# Power.net
KiCad netlist of a schematic drawn in Altium Designer
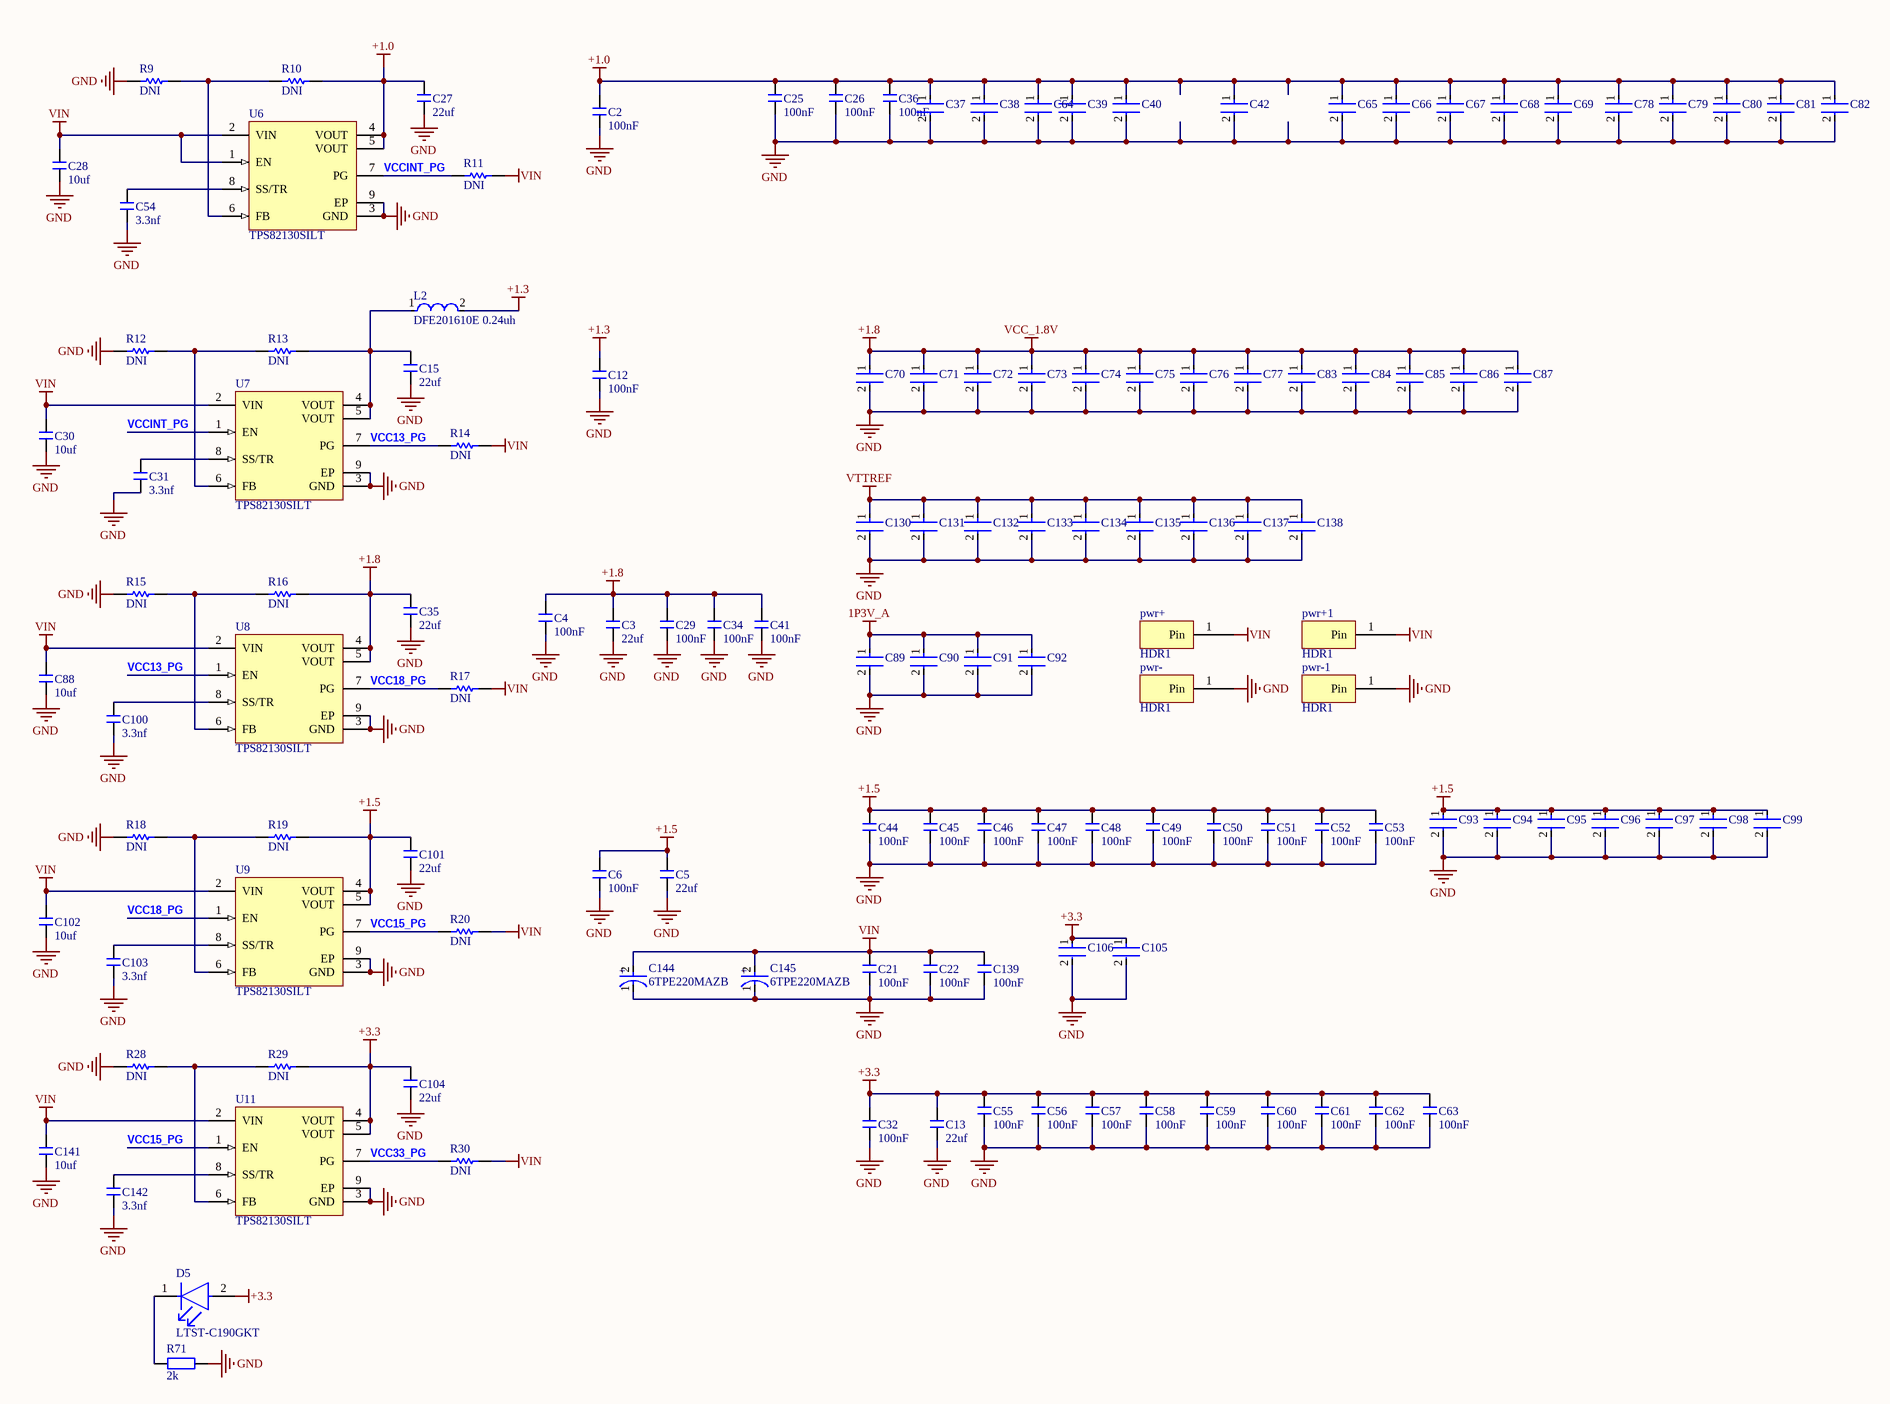
[diagram p0: Power.SchDoc]

(export (version "E")
  (design (tool "Eeschema 10.0.6"))
  (components
    (comp (ref "C2")
      (value "100nF")
      (footprint "SamacSys:CAP_0402")
      (description "无极性贴片电容")
      (libsource (lib "源创客") (part "C"))
    )
    (comp (ref "C3")
      (value "22uf")
      (footprint "SamacSys:CAP_0603")
      (description "无极性贴片电容")
      (libsource (lib "源创客") (part "C"))
    )
    (comp (ref "C4")
      (value "100nF")
      (footprint "SamacSys:CAP_0402")
      (description "无极性贴片电容")
      (libsource (lib "源创客") (part "C"))
    )
    (comp (ref "C5")
      (value "22uf")
      (footprint "SamacSys:CAP_0603")
      (description "无极性贴片电容")
      (libsource (lib "源创客") (part "C"))
    )
    (comp (ref "C6")
      (value "100nF")
      (footprint "SamacSys:CAP_0402")
      (description "无极性贴片电容")
      (libsource (lib "源创客") (part "C"))
    )
    (comp (ref "C12")
      (value "100nF")
      (footprint "SamacSys:CAP_0402")
      (description "无极性贴片电容")
      (libsource (lib "源创客") (part "C"))
    )
    (comp (ref "C13")
      (value "22uf")
      (footprint "SamacSys:CAP_0603")
      (description "无极性贴片电容")
      (libsource (lib "源创客") (part "C"))
    )
    (comp (ref "C15")
      (value "22uf")
      (footprint "SamacSys:CAP_0603")
      (description "无极性贴片电容")
      (libsource (lib "源创客") (part "C"))
    )
    (comp (ref "C21")
      (value "100nF")
      (footprint "SamacSys:CAP_0402")
      (description "无极性贴片电容")
      (libsource (lib "源创客") (part "C"))
    )
    (comp (ref "C22")
      (value "100nF")
      (footprint "SamacSys:CAP_0402")
      (description "无极性贴片电容")
      (libsource (lib "源创客") (part "C"))
    )
    (comp (ref "C25")
      (value "100nF")
      (footprint "SamacSys:CAP_0402")
      (description "无极性贴片电容")
      (libsource (lib "源创客") (part "C"))
    )
    (comp (ref "C26")
      (value "100nF")
      (footprint "SamacSys:CAP_0402")
      (description "无极性贴片电容")
      (libsource (lib "源创客") (part "C"))
    )
    (comp (ref "C27")
      (value "22uf")
      (footprint "SamacSys:CAP_0603")
      (description "无极性贴片电容")
      (libsource (lib "源创客") (part "C"))
    )
    (comp (ref "C28")
      (value "10uf")
      (footprint "SamacSys:CAP_0603")
      (description "无极性贴片电容")
      (libsource (lib "源创客") (part "C"))
    )
    (comp (ref "C29")
      (value "100nF")
      (footprint "SamacSys:CAP_0201")
      (description "无极性贴片电容")
      (libsource (lib "源创客") (part "C"))
    )
    (comp (ref "C30")
      (value "10uf")
      (footprint "SamacSys:CAP_0603")
      (description "无极性贴片电容")
      (libsource (lib "源创客") (part "C"))
    )
    (comp (ref "C31")
      (value "3.3nf")
      (footprint "SamacSys:CAP_0402")
      (description "无极性贴片电容")
      (libsource (lib "源创客") (part "C"))
    )
    (comp (ref "C32")
      (value "100nF")
      (footprint "SamacSys:CAP_0201")
      (description "无极性贴片电容")
      (libsource (lib "源创客") (part "C"))
    )
    (comp (ref "C34")
      (value "100nF")
      (footprint "SamacSys:CAP_0201")
      (description "无极性贴片电容")
      (libsource (lib "源创客") (part "C"))
    )
    (comp (ref "C35")
      (value "22uf")
      (footprint "SamacSys:CAP_0603")
      (description "无极性贴片电容")
      (libsource (lib "源创客") (part "C"))
    )
    (comp (ref "C36")
      (value "100nF")
      (footprint "SamacSys:CAP_0402")
      (description "无极性贴片电容")
      (libsource (lib "源创客") (part "C"))
    )
    (comp (ref "C37")
      (value "GRM033R61A104KE15D")
      (footprint "FP-GRM033-0_03-IPC_C")
      (description "Chip Multilayer Ceramic Capacitors for General Purpose, 0201, 0.10uF, X5R, 15%, 10%, 10V")
      (fields (field (name "TOLERANCE") "10%") (field (name "VOLTAGE") "10V"))
      (libsource (lib "Altium Content Vault") (part "b4654b650e69147ec39a6b967a45e02"))
    )
    (comp (ref "C38")
      (value "GRM033R61A104KE15D")
      (footprint "FP-GRM033-0_03-IPC_C")
      (description "Chip Multilayer Ceramic Capacitors for General Purpose, 0201, 0.10uF, X5R, 15%, 10%, 10V")
      (fields (field (name "TOLERANCE") "10%") (field (name "VOLTAGE") "10V"))
      (libsource (lib "Altium Content Vault") (part "b4654b650e69147ec39a6b967a45e02"))
    )
    (comp (ref "C39")
      (value "GRM033R61A104KE15D")
      (footprint "FP-GRM033-0_03-IPC_C")
      (description "Chip Multilayer Ceramic Capacitors for General Purpose, 0201, 0.10uF, X5R, 15%, 10%, 10V")
      (fields (field (name "TOLERANCE") "10%") (field (name "VOLTAGE") "10V"))
      (libsource (lib "Altium Content Vault") (part "b4654b650e69147ec39a6b967a45e02"))
    )
    (comp (ref "C40")
      (value "GRM033R61A104KE15D")
      (footprint "FP-GRM033-0_03-IPC_C")
      (description "Chip Multilayer Ceramic Capacitors for General Purpose, 0201, 0.10uF, X5R, 15%, 10%, 10V")
      (fields (field (name "TOLERANCE") "10%") (field (name "VOLTAGE") "10V"))
      (libsource (lib "Altium Content Vault") (part "b4654b650e69147ec39a6b967a45e02"))
    )
    (comp (ref "C41")
      (value "100nF")
      (footprint "SamacSys:CAP_0201")
      (description "无极性贴片电容")
      (libsource (lib "源创客") (part "C"))
    )
    (comp (ref "C42")
      (value "GRM033R61A104KE15D")
      (footprint "FP-GRM033-0_03-IPC_C")
      (description "Chip Multilayer Ceramic Capacitors for General Purpose, 0201, 0.10uF, X5R, 15%, 10%, 10V")
      (fields (field (name "TOLERANCE") "10%") (field (name "VOLTAGE") "10V"))
      (libsource (lib "Altium Content Vault") (part "b4654b650e69147ec39a6b967a45e02"))
    )
    (comp (ref "C44")
      (value "100nF")
      (footprint "SamacSys:CAP_0402")
      (description "无极性贴片电容")
      (libsource (lib "源创客") (part "C"))
    )
    (comp (ref "C45")
      (value "100nF")
      (footprint "SamacSys:CAP_0402")
      (description "无极性贴片电容")
      (libsource (lib "源创客") (part "C"))
    )
    (comp (ref "C46")
      (value "100nF")
      (footprint "SamacSys:CAP_0402")
      (description "无极性贴片电容")
      (libsource (lib "源创客") (part "C"))
    )
    (comp (ref "C47")
      (value "100nF")
      (footprint "SamacSys:CAP_0402")
      (description "无极性贴片电容")
      (libsource (lib "源创客") (part "C"))
    )
    (comp (ref "C48")
      (value "100nF")
      (footprint "SamacSys:CAP_0402")
      (description "无极性贴片电容")
      (libsource (lib "源创客") (part "C"))
    )
    (comp (ref "C49")
      (value "100nF")
      (footprint "SamacSys:CAP_0402")
      (description "无极性贴片电容")
      (libsource (lib "源创客") (part "C"))
    )
    (comp (ref "C50")
      (value "100nF")
      (footprint "SamacSys:CAP_0402")
      (description "无极性贴片电容")
      (libsource (lib "源创客") (part "C"))
    )
    (comp (ref "C51")
      (value "100nF")
      (footprint "SamacSys:CAP_0402")
      (description "无极性贴片电容")
      (libsource (lib "源创客") (part "C"))
    )
    (comp (ref "C52")
      (value "100nF")
      (footprint "SamacSys:CAP_0402")
      (description "无极性贴片电容")
      (libsource (lib "源创客") (part "C"))
    )
    (comp (ref "C53")
      (value "100nF")
      (footprint "SamacSys:CAP_0402")
      (description "无极性贴片电容")
      (libsource (lib "源创客") (part "C"))
    )
    (comp (ref "C54")
      (value "3.3nf")
      (footprint "SamacSys:CAP_0402")
      (description "无极性贴片电容")
      (libsource (lib "源创客") (part "C"))
    )
    (comp (ref "C55")
      (value "100nF")
      (footprint "SamacSys:CAP_0402")
      (description "无极性贴片电容")
      (libsource (lib "源创客") (part "C"))
    )
    (comp (ref "C56")
      (value "100nF")
      (footprint "SamacSys:CAP_0402")
      (description "无极性贴片电容")
      (libsource (lib "源创客") (part "C"))
    )
    (comp (ref "C57")
      (value "100nF")
      (footprint "SamacSys:CAP_0402")
      (description "无极性贴片电容")
      (libsource (lib "源创客") (part "C"))
    )
    (comp (ref "C58")
      (value "100nF")
      (footprint "SamacSys:CAP_0402")
      (description "无极性贴片电容")
      (libsource (lib "源创客") (part "C"))
    )
    (comp (ref "C59")
      (value "100nF")
      (footprint "SamacSys:CAP_0201")
      (description "无极性贴片电容")
      (libsource (lib "源创客") (part "C"))
    )
    (comp (ref "C60")
      (value "100nF")
      (footprint "SamacSys:CAP_0201")
      (description "无极性贴片电容")
      (libsource (lib "源创客") (part "C"))
    )
    (comp (ref "C61")
      (value "100nF")
      (footprint "SamacSys:CAP_0201")
      (description "无极性贴片电容")
      (libsource (lib "源创客") (part "C"))
    )
    (comp (ref "C62")
      (value "100nF")
      (footprint "SamacSys:CAP_0402")
      (description "无极性贴片电容")
      (libsource (lib "源创客") (part "C"))
    )
    (comp (ref "C63")
      (value "100nF")
      (footprint "SamacSys:CAP_0402")
      (description "无极性贴片电容")
      (libsource (lib "源创客") (part "C"))
    )
    (comp (ref "C64")
      (value "GRM033R61A104KE15D")
      (footprint "FP-GRM033-0_03-IPC_C")
      (description "Chip Multilayer Ceramic Capacitors for General Purpose, 0201, 0.10uF, X5R, 15%, 10%, 10V")
      (fields (field (name "TOLERANCE") "10%") (field (name "VOLTAGE") "10V"))
      (libsource (lib "Altium Content Vault") (part "b4654b650e69147ec39a6b967a45e02"))
    )
    (comp (ref "C65")
      (value "GRM033R61A104KE15D")
      (footprint "FP-GRM033-0_03-IPC_C")
      (description "Chip Multilayer Ceramic Capacitors for General Purpose, 0201, 0.10uF, X5R, 15%, 10%, 10V")
      (fields (field (name "TOLERANCE") "10%") (field (name "VOLTAGE") "10V"))
      (libsource (lib "Altium Content Vault") (part "b4654b650e69147ec39a6b967a45e02"))
    )
    (comp (ref "C66")
      (value "GRM033R61A104KE15D")
      (footprint "FP-GRM033-0_03-IPC_C")
      (description "Chip Multilayer Ceramic Capacitors for General Purpose, 0201, 0.10uF, X5R, 15%, 10%, 10V")
      (fields (field (name "TOLERANCE") "10%") (field (name "VOLTAGE") "10V"))
      (libsource (lib "Altium Content Vault") (part "b4654b650e69147ec39a6b967a45e02"))
    )
    (comp (ref "C67")
      (value "GRM033R61A104KE15D")
      (footprint "FP-GRM033-0_03-IPC_C")
      (description "Chip Multilayer Ceramic Capacitors for General Purpose, 0201, 0.10uF, X5R, 15%, 10%, 10V")
      (fields (field (name "TOLERANCE") "10%") (field (name "VOLTAGE") "10V"))
      (libsource (lib "Altium Content Vault") (part "b4654b650e69147ec39a6b967a45e02"))
    )
    (comp (ref "C68")
      (value "GRM033R61A104KE15D")
      (footprint "FP-GRM033-0_03-IPC_C")
      (description "Chip Multilayer Ceramic Capacitors for General Purpose, 0201, 0.10uF, X5R, 15%, 10%, 10V")
      (fields (field (name "TOLERANCE") "10%") (field (name "VOLTAGE") "10V"))
      (libsource (lib "Altium Content Vault") (part "b4654b650e69147ec39a6b967a45e02"))
    )
    (comp (ref "C69")
      (value "GRM033R61A104KE15D")
      (footprint "FP-GRM033-0_03-IPC_C")
      (description "Chip Multilayer Ceramic Capacitors for General Purpose, 0201, 0.10uF, X5R, 15%, 10%, 10V")
      (fields (field (name "TOLERANCE") "10%") (field (name "VOLTAGE") "10V"))
      (libsource (lib "Altium Content Vault") (part "b4654b650e69147ec39a6b967a45e02"))
    )
    (comp (ref "C70")
      (value "GRM033R61A104KE15D")
      (footprint "FP-GRM033-0_03-IPC_C")
      (description "Chip Multilayer Ceramic Capacitors for General Purpose, 0201, 0.10uF, X5R, 15%, 10%, 10V")
      (fields (field (name "TOLERANCE") "10%") (field (name "VOLTAGE") "10V"))
      (libsource (lib "Altium Content Vault") (part "b4654b650e69147ec39a6b967a45e02"))
    )
    (comp (ref "C71")
      (value "GRM033R61A104KE15D")
      (footprint "FP-GRM033-0_03-IPC_C")
      (description "Chip Multilayer Ceramic Capacitors for General Purpose, 0201, 0.10uF, X5R, 15%, 10%, 10V")
      (fields (field (name "TOLERANCE") "10%") (field (name "VOLTAGE") "10V"))
      (libsource (lib "Altium Content Vault") (part "b4654b650e69147ec39a6b967a45e02"))
    )
    (comp (ref "C72")
      (value "GRM033R61A104KE15D")
      (footprint "FP-GRM033-0_03-IPC_C")
      (description "Chip Multilayer Ceramic Capacitors for General Purpose, 0201, 0.10uF, X5R, 15%, 10%, 10V")
      (fields (field (name "TOLERANCE") "10%") (field (name "VOLTAGE") "10V"))
      (libsource (lib "Altium Content Vault") (part "b4654b650e69147ec39a6b967a45e02"))
    )
    (comp (ref "C73")
      (value "GRM033R61A104KE15D")
      (footprint "FP-GRM033-0_03-IPC_C")
      (description "Chip Multilayer Ceramic Capacitors for General Purpose, 0201, 0.10uF, X5R, 15%, 10%, 10V")
      (fields (field (name "TOLERANCE") "10%") (field (name "VOLTAGE") "10V"))
      (libsource (lib "Altium Content Vault") (part "b4654b650e69147ec39a6b967a45e02"))
    )
    (comp (ref "C74")
      (value "GRM033R61A104KE15D")
      (footprint "FP-GRM033-0_03-IPC_C")
      (description "Chip Multilayer Ceramic Capacitors for General Purpose, 0201, 0.10uF, X5R, 15%, 10%, 10V")
      (fields (field (name "TOLERANCE") "10%") (field (name "VOLTAGE") "10V"))
      (libsource (lib "Altium Content Vault") (part "b4654b650e69147ec39a6b967a45e02"))
    )
    (comp (ref "C75")
      (value "GRM033R61A104KE15D")
      (footprint "FP-GRM033-0_03-IPC_C")
      (description "Chip Multilayer Ceramic Capacitors for General Purpose, 0201, 0.10uF, X5R, 15%, 10%, 10V")
      (fields (field (name "TOLERANCE") "10%") (field (name "VOLTAGE") "10V"))
      (libsource (lib "Altium Content Vault") (part "b4654b650e69147ec39a6b967a45e02"))
    )
    (comp (ref "C76")
      (value "GRM033R61A104KE15D")
      (footprint "FP-GRM033-0_03-IPC_C")
      (description "Chip Multilayer Ceramic Capacitors for General Purpose, 0201, 0.10uF, X5R, 15%, 10%, 10V")
      (fields (field (name "TOLERANCE") "10%") (field (name "VOLTAGE") "10V"))
      (libsource (lib "Altium Content Vault") (part "b4654b650e69147ec39a6b967a45e02"))
    )
    (comp (ref "C77")
      (value "GRM033R61A104KE15D")
      (footprint "FP-GRM033-0_03-IPC_C")
      (description "Chip Multilayer Ceramic Capacitors for General Purpose, 0201, 0.10uF, X5R, 15%, 10%, 10V")
      (fields (field (name "TOLERANCE") "10%") (field (name "VOLTAGE") "10V"))
      (libsource (lib "Altium Content Vault") (part "b4654b650e69147ec39a6b967a45e02"))
    )
    (comp (ref "C78")
      (value "GRM033R61A104KE15D")
      (footprint "FP-GRM033-0_03-IPC_C")
      (description "Chip Multilayer Ceramic Capacitors for General Purpose, 0201, 0.10uF, X5R, 15%, 10%, 10V")
      (fields (field (name "TOLERANCE") "10%") (field (name "VOLTAGE") "10V"))
      (libsource (lib "Altium Content Vault") (part "b4654b650e69147ec39a6b967a45e02"))
    )
    (comp (ref "C79")
      (value "GRM033R61A104KE15D")
      (footprint "FP-GRM033-0_03-IPC_C")
      (description "Chip Multilayer Ceramic Capacitors for General Purpose, 0201, 0.10uF, X5R, 15%, 10%, 10V")
      (fields (field (name "TOLERANCE") "10%") (field (name "VOLTAGE") "10V"))
      (libsource (lib "Altium Content Vault") (part "b4654b650e69147ec39a6b967a45e02"))
    )
    (comp (ref "C80")
      (value "GRM033R61A104KE15D")
      (footprint "FP-GRM033-0_03-IPC_C")
      (description "Chip Multilayer Ceramic Capacitors for General Purpose, 0201, 0.10uF, X5R, 15%, 10%, 10V")
      (fields (field (name "TOLERANCE") "10%") (field (name "VOLTAGE") "10V"))
      (libsource (lib "Altium Content Vault") (part "b4654b650e69147ec39a6b967a45e02"))
    )
    (comp (ref "C81")
      (value "GRM033R61A104KE15D")
      (footprint "FP-GRM033-0_03-IPC_C")
      (description "Chip Multilayer Ceramic Capacitors for General Purpose, 0201, 0.10uF, X5R, 15%, 10%, 10V")
      (fields (field (name "TOLERANCE") "10%") (field (name "VOLTAGE") "10V"))
      (libsource (lib "Altium Content Vault") (part "b4654b650e69147ec39a6b967a45e02"))
    )
    (comp (ref "C82")
      (value "GRM033R61A104KE15D")
      (footprint "FP-GRM033-0_03-IPC_C")
      (description "Chip Multilayer Ceramic Capacitors for General Purpose, 0201, 0.10uF, X5R, 15%, 10%, 10V")
      (fields (field (name "TOLERANCE") "10%") (field (name "VOLTAGE") "10V"))
      (libsource (lib "Altium Content Vault") (part "b4654b650e69147ec39a6b967a45e02"))
    )
    (comp (ref "C83")
      (value "GRM033R61A104KE15D")
      (footprint "FP-GRM033-0_03-IPC_C")
      (description "Chip Multilayer Ceramic Capacitors for General Purpose, 0201, 0.10uF, X5R, 15%, 10%, 10V")
      (fields (field (name "TOLERANCE") "10%") (field (name "VOLTAGE") "10V"))
      (libsource (lib "Altium Content Vault") (part "b4654b650e69147ec39a6b967a45e02"))
    )
    (comp (ref "C84")
      (value "GRM033R61A104KE15D")
      (footprint "FP-GRM033-0_03-IPC_C")
      (description "Chip Multilayer Ceramic Capacitors for General Purpose, 0201, 0.10uF, X5R, 15%, 10%, 10V")
      (fields (field (name "TOLERANCE") "10%") (field (name "VOLTAGE") "10V"))
      (libsource (lib "Altium Content Vault") (part "b4654b650e69147ec39a6b967a45e02"))
    )
    (comp (ref "C85")
      (value "GRM033R61A104KE15D")
      (footprint "FP-GRM033-0_03-IPC_C")
      (description "Chip Multilayer Ceramic Capacitors for General Purpose, 0201, 0.10uF, X5R, 15%, 10%, 10V")
      (fields (field (name "TOLERANCE") "10%") (field (name "VOLTAGE") "10V"))
      (libsource (lib "Altium Content Vault") (part "b4654b650e69147ec39a6b967a45e02"))
    )
    (comp (ref "C86")
      (value "GRM033R61A104KE15D")
      (footprint "FP-GRM033-0_03-IPC_C")
      (description "Chip Multilayer Ceramic Capacitors for General Purpose, 0201, 0.10uF, X5R, 15%, 10%, 10V")
      (fields (field (name "TOLERANCE") "10%") (field (name "VOLTAGE") "10V"))
      (libsource (lib "Altium Content Vault") (part "b4654b650e69147ec39a6b967a45e02"))
    )
    (comp (ref "C87")
      (value "GRM033R61A104KE15D")
      (footprint "FP-GRM033-0_03-IPC_C")
      (description "Chip Multilayer Ceramic Capacitors for General Purpose, 0201, 0.10uF, X5R, 15%, 10%, 10V")
      (fields (field (name "TOLERANCE") "10%") (field (name "VOLTAGE") "10V"))
      (libsource (lib "Altium Content Vault") (part "b4654b650e69147ec39a6b967a45e02"))
    )
    (comp (ref "C88")
      (value "10uf")
      (footprint "SamacSys:CAP_0603")
      (description "无极性贴片电容")
      (libsource (lib "源创客") (part "C"))
    )
    (comp (ref "C89")
      (value "GRM033R61A104KE15D")
      (footprint "FP-GRM033-0_03-IPC_C")
      (description "Chip Multilayer Ceramic Capacitors for General Purpose, 0201, 0.10uF, X5R, 15%, 10%, 10V")
      (fields (field (name "TOLERANCE") "10%") (field (name "VOLTAGE") "10V"))
      (libsource (lib "Altium Content Vault") (part "b4654b650e69147ec39a6b967a45e02"))
    )
    (comp (ref "C90")
      (value "GRM033R61A104KE15D")
      (footprint "FP-GRM033-0_03-IPC_C")
      (description "Chip Multilayer Ceramic Capacitors for General Purpose, 0201, 0.10uF, X5R, 15%, 10%, 10V")
      (fields (field (name "TOLERANCE") "10%") (field (name "VOLTAGE") "10V"))
      (libsource (lib "Altium Content Vault") (part "b4654b650e69147ec39a6b967a45e02"))
    )
    (comp (ref "C91")
      (value "GRM033R61A104KE15D")
      (footprint "FP-GRM033-0_03-IPC_C")
      (description "Chip Multilayer Ceramic Capacitors for General Purpose, 0201, 0.10uF, X5R, 15%, 10%, 10V")
      (fields (field (name "TOLERANCE") "10%") (field (name "VOLTAGE") "10V"))
      (libsource (lib "Altium Content Vault") (part "b4654b650e69147ec39a6b967a45e02"))
    )
    (comp (ref "C92")
      (value "GRM033R61A104KE15D")
      (footprint "FP-GRM033-0_03-IPC_C")
      (description "Chip Multilayer Ceramic Capacitors for General Purpose, 0201, 0.10uF, X5R, 15%, 10%, 10V")
      (fields (field (name "TOLERANCE") "10%") (field (name "VOLTAGE") "10V"))
      (libsource (lib "Altium Content Vault") (part "b4654b650e69147ec39a6b967a45e02"))
    )
    (comp (ref "C93")
      (value "GRM033R61A104KE15D")
      (footprint "FP-GRM033-0_03-IPC_C")
      (description "Chip Multilayer Ceramic Capacitors for General Purpose, 0201, 0.10uF, X5R, 15%, 10%, 10V")
      (fields (field (name "TOLERANCE") "10%") (field (name "VOLTAGE") "10V"))
      (libsource (lib "Altium Content Vault") (part "b4654b650e69147ec39a6b967a45e02"))
    )
    (comp (ref "C94")
      (value "GRM033R61A104KE15D")
      (footprint "FP-GRM033-0_03-IPC_C")
      (description "Chip Multilayer Ceramic Capacitors for General Purpose, 0201, 0.10uF, X5R, 15%, 10%, 10V")
      (fields (field (name "TOLERANCE") "10%") (field (name "VOLTAGE") "10V"))
      (libsource (lib "Altium Content Vault") (part "b4654b650e69147ec39a6b967a45e02"))
    )
    (comp (ref "C95")
      (value "GRM033R61A104KE15D")
      (footprint "FP-GRM033-0_03-IPC_C")
      (description "Chip Multilayer Ceramic Capacitors for General Purpose, 0201, 0.10uF, X5R, 15%, 10%, 10V")
      (fields (field (name "TOLERANCE") "10%") (field (name "VOLTAGE") "10V"))
      (libsource (lib "Altium Content Vault") (part "b4654b650e69147ec39a6b967a45e02"))
    )
    (comp (ref "C96")
      (value "GRM033R61A104KE15D")
      (footprint "FP-GRM033-0_03-IPC_C")
      (description "Chip Multilayer Ceramic Capacitors for General Purpose, 0201, 0.10uF, X5R, 15%, 10%, 10V")
      (fields (field (name "TOLERANCE") "10%") (field (name "VOLTAGE") "10V"))
      (libsource (lib "Altium Content Vault") (part "b4654b650e69147ec39a6b967a45e02"))
    )
    (comp (ref "C97")
      (value "GRM033R61A104KE15D")
      (footprint "FP-GRM033-0_03-IPC_C")
      (description "Chip Multilayer Ceramic Capacitors for General Purpose, 0201, 0.10uF, X5R, 15%, 10%, 10V")
      (fields (field (name "TOLERANCE") "10%") (field (name "VOLTAGE") "10V"))
      (libsource (lib "Altium Content Vault") (part "b4654b650e69147ec39a6b967a45e02"))
    )
    (comp (ref "C98")
      (value "GRM033R61A104KE15D")
      (footprint "FP-GRM033-0_03-IPC_C")
      (description "Chip Multilayer Ceramic Capacitors for General Purpose, 0201, 0.10uF, X5R, 15%, 10%, 10V")
      (fields (field (name "TOLERANCE") "10%") (field (name "VOLTAGE") "10V"))
      (libsource (lib "Altium Content Vault") (part "b4654b650e69147ec39a6b967a45e02"))
    )
    (comp (ref "C99")
      (value "GRM033R61A104KE15D")
      (footprint "FP-GRM033-0_03-IPC_C")
      (description "Chip Multilayer Ceramic Capacitors for General Purpose, 0201, 0.10uF, X5R, 15%, 10%, 10V")
      (fields (field (name "TOLERANCE") "10%") (field (name "VOLTAGE") "10V"))
      (libsource (lib "Altium Content Vault") (part "b4654b650e69147ec39a6b967a45e02"))
    )
    (comp (ref "C100")
      (value "3.3nf")
      (footprint "SamacSys:CAP_0402")
      (description "无极性贴片电容")
      (libsource (lib "源创客") (part "C"))
    )
    (comp (ref "C101")
      (value "22uf")
      (footprint "SamacSys:CAP_0603")
      (description "无极性贴片电容")
      (libsource (lib "源创客") (part "C"))
    )
    (comp (ref "C102")
      (value "10uf")
      (footprint "SamacSys:CAP_0603")
      (description "无极性贴片电容")
      (libsource (lib "源创客") (part "C"))
    )
    (comp (ref "C103")
      (value "3.3nf")
      (footprint "SamacSys:CAP_0402")
      (description "无极性贴片电容")
      (libsource (lib "源创客") (part "C"))
    )
    (comp (ref "C104")
      (value "22uf")
      (footprint "SamacSys:CAP_0603")
      (description "无极性贴片电容")
      (libsource (lib "源创客") (part "C"))
    )
    (comp (ref "C105")
      (value "GRM033R61A104KE15D")
      (footprint "FP-GRM033-0_03-IPC_C")
      (description "Chip Multilayer Ceramic Capacitors for General Purpose, 0201, 0.10uF, X5R, 15%, 10%, 10V")
      (fields (field (name "TOLERANCE") "10%") (field (name "VOLTAGE") "10V"))
      (libsource (lib "Altium Content Vault") (part "b4654b650e69147ec39a6b967a45e02"))
    )
    (comp (ref "C106")
      (value "GRM033R61A104KE15D")
      (footprint "FP-GRM033-0_03-IPC_C")
      (description "Chip Multilayer Ceramic Capacitors for General Purpose, 0201, 0.10uF, X5R, 15%, 10%, 10V")
      (fields (field (name "TOLERANCE") "10%") (field (name "VOLTAGE") "10V"))
      (libsource (lib "Altium Content Vault") (part "b4654b650e69147ec39a6b967a45e02"))
    )
    (comp (ref "C130")
      (value "GRM033R61A104KE15D")
      (footprint "FP-GRM033-0_03-IPC_C")
      (description "Chip Multilayer Ceramic Capacitors for General Purpose, 0201, 0.10uF, X5R, 15%, 10%, 10V")
      (fields (field (name "TOLERANCE") "10%") (field (name "VOLTAGE") "10V"))
      (libsource (lib "Altium Content Vault") (part "b4654b650e69147ec39a6b967a45e02"))
    )
    (comp (ref "C131")
      (value "GRM033R61A104KE15D")
      (footprint "FP-GRM033-0_03-IPC_C")
      (description "Chip Multilayer Ceramic Capacitors for General Purpose, 0201, 0.10uF, X5R, 15%, 10%, 10V")
      (fields (field (name "TOLERANCE") "10%") (field (name "VOLTAGE") "10V"))
      (libsource (lib "Altium Content Vault") (part "b4654b650e69147ec39a6b967a45e02"))
    )
    (comp (ref "C132")
      (value "GRM033R61A104KE15D")
      (footprint "FP-GRM033-0_03-IPC_C")
      (description "Chip Multilayer Ceramic Capacitors for General Purpose, 0201, 0.10uF, X5R, 15%, 10%, 10V")
      (fields (field (name "TOLERANCE") "10%") (field (name "VOLTAGE") "10V"))
      (libsource (lib "Altium Content Vault") (part "b4654b650e69147ec39a6b967a45e02"))
    )
    (comp (ref "C133")
      (value "GRM033R61A104KE15D")
      (footprint "FP-GRM033-0_03-IPC_C")
      (description "Chip Multilayer Ceramic Capacitors for General Purpose, 0201, 0.10uF, X5R, 15%, 10%, 10V")
      (fields (field (name "TOLERANCE") "10%") (field (name "VOLTAGE") "10V"))
      (libsource (lib "Altium Content Vault") (part "b4654b650e69147ec39a6b967a45e02"))
    )
    (comp (ref "C134")
      (value "GRM033R61A104KE15D")
      (footprint "FP-GRM033-0_03-IPC_C")
      (description "Chip Multilayer Ceramic Capacitors for General Purpose, 0201, 0.10uF, X5R, 15%, 10%, 10V")
      (fields (field (name "TOLERANCE") "10%") (field (name "VOLTAGE") "10V"))
      (libsource (lib "Altium Content Vault") (part "b4654b650e69147ec39a6b967a45e02"))
    )
    (comp (ref "C135")
      (value "GRM033R61A104KE15D")
      (footprint "FP-GRM033-0_03-IPC_C")
      (description "Chip Multilayer Ceramic Capacitors for General Purpose, 0201, 0.10uF, X5R, 15%, 10%, 10V")
      (fields (field (name "TOLERANCE") "10%") (field (name "VOLTAGE") "10V"))
      (libsource (lib "Altium Content Vault") (part "b4654b650e69147ec39a6b967a45e02"))
    )
    (comp (ref "C136")
      (value "GRM033R61A104KE15D")
      (footprint "FP-GRM033-0_03-IPC_C")
      (description "Chip Multilayer Ceramic Capacitors for General Purpose, 0201, 0.10uF, X5R, 15%, 10%, 10V")
      (fields (field (name "TOLERANCE") "10%") (field (name "VOLTAGE") "10V"))
      (libsource (lib "Altium Content Vault") (part "b4654b650e69147ec39a6b967a45e02"))
    )
    (comp (ref "C137")
      (value "GRM033R61A104KE15D")
      (footprint "FP-GRM033-0_03-IPC_C")
      (description "Chip Multilayer Ceramic Capacitors for General Purpose, 0201, 0.10uF, X5R, 15%, 10%, 10V")
      (fields (field (name "TOLERANCE") "10%") (field (name "VOLTAGE") "10V"))
      (libsource (lib "Altium Content Vault") (part "b4654b650e69147ec39a6b967a45e02"))
    )
    (comp (ref "C138")
      (value "GRM033R61A104KE15D")
      (footprint "FP-GRM033-0_03-IPC_C")
      (description "Chip Multilayer Ceramic Capacitors for General Purpose, 0201, 0.10uF, X5R, 15%, 10%, 10V")
      (fields (field (name "TOLERANCE") "10%") (field (name "VOLTAGE") "10V"))
      (libsource (lib "Altium Content Vault") (part "b4654b650e69147ec39a6b967a45e02"))
    )
    (comp (ref "C139")
      (value "100nF")
      (footprint "SamacSys:CAP_0402")
      (description "无极性贴片电容")
      (libsource (lib "源创客") (part "C"))
    )
    (comp (ref "C141")
      (value "10uf")
      (footprint "SamacSys:CAP_0603")
      (description "无极性贴片电容")
      (libsource (lib "源创客") (part "C"))
    )
    (comp (ref "C142")
      (value "3.3nf")
      (footprint "SamacSys:CAP_0402")
      (description "无极性贴片电容")
      (libsource (lib "源创客") (part "C"))
    )
    (comp (ref "C144")
      (value "6TPE220MAZB")
      (footprint "FP-TPEB2-MFG")
      (description "CAP TANT POLY 220UF 6.3V 1411")
      (fields (field (name "TOLERANCE") "20%") (field (name "VOLTAGE") "6.3V"))
      (libsource (lib "Altium Content Vault") (part "a00bbbee19879c290e62620ae7e47b1"))
    )
    (comp (ref "C145")
      (value "6TPE220MAZB")
      (footprint "FP-TPEB2-MFG")
      (description "CAP TANT POLY 220UF 6.3V 1411")
      (fields (field (name "TOLERANCE") "20%") (field (name "VOLTAGE") "6.3V"))
      (libsource (lib "Altium Content Vault") (part "a00bbbee19879c290e62620ae7e47b1"))
    )
    (comp (ref "D5")
      (value "LTST-C190GKT")
      (footprint "FP-LTST-C190GKT-MFG")
      (description "LED GREEN CLEAR CHIP SMD")
      (fields (field (name "VOLTAGE") "2V"))
      (libsource (lib "Altium Content Vault") (part "8706943c75ba83719d021d2fdc84c58"))
    )
    (comp (ref "L2")
      (value "DFE201610E 0.24uh")
      (footprint "FP-DFE201610C-MFG")
      (description "0.24uh")
      (libsource (lib "Altium Content Vault") (part "725321dda6339637d4d059423bc1c3c"))
    )
    (comp (ref "pwr+") (value "HDR1") (footprint "SamacSys:HDR1") (libsource (lib "SamacSys") (part "HDR1")))
    (comp (ref "pwr+1") (value "HDR1") (footprint "SamacSys:HDR1") (libsource (lib "SamacSys") (part "HDR1")))
    (comp (ref "pwr-") (value "HDR1") (footprint "SamacSys:HDR1") (libsource (lib "SamacSys") (part "HDR1")))
    (comp (ref "pwr-1") (value "HDR1") (footprint "SamacSys:HDR1") (libsource (lib "SamacSys") (part "HDR1")))
    (comp (ref "R9") (value "DNI") (footprint "SamacSys:RES_0402") (libsource (lib "电阻") (part "RES")))
    (comp (ref "R10") (value "DNI") (footprint "SamacSys:RES_0402") (libsource (lib "电阻") (part "RES")))
    (comp (ref "R11") (value "DNI") (footprint "SamacSys:RES_0402") (libsource (lib "电阻") (part "RES")))
    (comp (ref "R12") (value "DNI") (footprint "SamacSys:RES_0402") (libsource (lib "电阻") (part "RES")))
    (comp (ref "R13") (value "DNI") (footprint "SamacSys:RES_0402") (libsource (lib "电阻") (part "RES")))
    (comp (ref "R14") (value "DNI") (footprint "SamacSys:RES_0402") (libsource (lib "电阻") (part "RES")))
    (comp (ref "R15") (value "DNI") (footprint "SamacSys:RES_0402") (libsource (lib "电阻") (part "RES")))
    (comp (ref "R16") (value "DNI") (footprint "SamacSys:RES_0402") (libsource (lib "电阻") (part "RES")))
    (comp (ref "R17") (value "DNI") (footprint "SamacSys:RES_0402") (libsource (lib "电阻") (part "RES")))
    (comp (ref "R18") (value "DNI") (footprint "SamacSys:RES_0402") (libsource (lib "电阻") (part "RES")))
    (comp (ref "R19") (value "DNI") (footprint "SamacSys:RES_0402") (libsource (lib "电阻") (part "RES")))
    (comp (ref "R20") (value "DNI") (footprint "SamacSys:RES_0402") (libsource (lib "电阻") (part "RES")))
    (comp (ref "R28") (value "DNI") (footprint "SamacSys:RES_0402") (libsource (lib "电阻") (part "RES")))
    (comp (ref "R29") (value "DNI") (footprint "SamacSys:RES_0402") (libsource (lib "电阻") (part "RES")))
    (comp (ref "R30") (value "DNI") (footprint "SamacSys:RES_0402") (libsource (lib "电阻") (part "RES")))
    (comp (ref "R71")
      (value "2k")
      (footprint "SamacSys:RES_0402")
      (description "贴片电阻")
      (libsource (lib "源创客") (part "R"))
    )
    (comp (ref "U6")
      (value "TPS82130SILT")
      (footprint "SIL0008D_V")
      (fields (field (name "MANUFACTURER") "Texas Instruments"))
      (libsource (lib "Altium Content Vault") (part "TI-TPS82130-SIL-8"))
    )
    (comp (ref "U7")
      (value "TPS82130SILT")
      (footprint "SIL0008D_V")
      (fields (field (name "MANUFACTURER") "Texas Instruments"))
      (libsource (lib "Altium Content Vault") (part "TI-TPS82130-SIL-8"))
    )
    (comp (ref "U8")
      (value "TPS82130SILT")
      (footprint "SIL0008D_V")
      (fields (field (name "MANUFACTURER") "Texas Instruments"))
      (libsource (lib "Altium Content Vault") (part "TI-TPS82130-SIL-8"))
    )
    (comp (ref "U9")
      (value "TPS82130SILT")
      (footprint "SIL0008D_V")
      (fields (field (name "MANUFACTURER") "Texas Instruments"))
      (libsource (lib "Altium Content Vault") (part "TI-TPS82130-SIL-8"))
    )
    (comp (ref "U11")
      (value "TPS82130SILT")
      (footprint "SIL0008D_V")
      (fields (field (name "MANUFACTURER") "Texas Instruments"))
      (libsource (lib "Altium Content Vault") (part "TI-TPS82130-SIL-8"))
    )
  )
  (nets
    (net (code "1") (name "+1.0") (class "Default")
      (node (ref "C2") (pin "1") (pinfunction "1_1") (pintype "passive"))
      (node (ref "C25") (pin "1") (pinfunction "1_1") (pintype "passive"))
      (node (ref "C26") (pin "1") (pinfunction "1_1") (pintype "passive"))
      (node (ref "C27") (pin "2") (pinfunction "2_2") (pintype "passive"))
      (node (ref "C36") (pin "1") (pinfunction "1_1") (pintype "passive"))
      (node (ref "C37") (pin "1") (pinfunction "1_1") (pintype "passive"))
      (node (ref "C38") (pin "1") (pinfunction "1_1") (pintype "passive"))
      (node (ref "C39") (pin "1") (pinfunction "1_1") (pintype "passive"))
      (node (ref "C40") (pin "1") (pinfunction "1_1") (pintype "passive"))
      (node (ref "C42") (pin "1") (pinfunction "1_1") (pintype "passive"))
      (node (ref "C64") (pin "1") (pinfunction "1_1") (pintype "passive"))
      (node (ref "C65") (pin "1") (pinfunction "1_1") (pintype "passive"))
      (node (ref "C66") (pin "1") (pinfunction "1_1") (pintype "passive"))
      (node (ref "C67") (pin "1") (pinfunction "1_1") (pintype "passive"))
      (node (ref "C68") (pin "1") (pinfunction "1_1") (pintype "passive"))
      (node (ref "C69") (pin "1") (pinfunction "1_1") (pintype "passive"))
      (node (ref "C78") (pin "1") (pinfunction "1_1") (pintype "passive"))
      (node (ref "C79") (pin "1") (pinfunction "1_1") (pintype "passive"))
      (node (ref "C80") (pin "1") (pinfunction "1_1") (pintype "passive"))
      (node (ref "C81") (pin "1") (pinfunction "1_1") (pintype "passive"))
      (node (ref "C82") (pin "1") (pinfunction "1_1") (pintype "passive"))
      (node (ref "R10") (pin "1") (pinfunction "1_1") (pintype "passive"))
      (node (ref "U6") (pin "4") (pinfunction "VOUT_4") (pintype "power_in"))
      (node (ref "U6") (pin "5") (pinfunction "VOUT_5") (pintype "power_in"))
    )
    (net (code "2") (name "+1.3") (class "Default")
      (node (ref "C12") (pin "1") (pinfunction "1_1") (pintype "passive"))
      (node (ref "L2") (pin "2") (pinfunction "2_2") (pintype "passive"))
    )
    (net (code "3") (name "+1.5") (class "Default")
      (node (ref "C101") (pin "2") (pinfunction "2_2") (pintype "passive"))
      (node (ref "C44") (pin "1") (pinfunction "1_1") (pintype "passive"))
      (node (ref "C45") (pin "1") (pinfunction "1_1") (pintype "passive"))
      (node (ref "C46") (pin "1") (pinfunction "1_1") (pintype "passive"))
      (node (ref "C47") (pin "1") (pinfunction "1_1") (pintype "passive"))
      (node (ref "C48") (pin "1") (pinfunction "1_1") (pintype "passive"))
      (node (ref "C49") (pin "1") (pinfunction "1_1") (pintype "passive"))
      (node (ref "C5") (pin "2") (pinfunction "2_2") (pintype "passive"))
      (node (ref "C50") (pin "1") (pinfunction "1_1") (pintype "passive"))
      (node (ref "C51") (pin "1") (pinfunction "1_1") (pintype "passive"))
      (node (ref "C52") (pin "1") (pinfunction "1_1") (pintype "passive"))
      (node (ref "C53") (pin "1") (pinfunction "1_1") (pintype "passive"))
      (node (ref "C6") (pin "1") (pinfunction "1_1") (pintype "passive"))
      (node (ref "C93") (pin "1") (pinfunction "1_1") (pintype "passive"))
      (node (ref "C94") (pin "1") (pinfunction "1_1") (pintype "passive"))
      (node (ref "C95") (pin "1") (pinfunction "1_1") (pintype "passive"))
      (node (ref "C96") (pin "1") (pinfunction "1_1") (pintype "passive"))
      (node (ref "C97") (pin "1") (pinfunction "1_1") (pintype "passive"))
      (node (ref "C98") (pin "1") (pinfunction "1_1") (pintype "passive"))
      (node (ref "C99") (pin "1") (pinfunction "1_1") (pintype "passive"))
      (node (ref "R19") (pin "1") (pinfunction "1_1") (pintype "passive"))
      (node (ref "U9") (pin "4") (pinfunction "VOUT_4") (pintype "power_in"))
      (node (ref "U9") (pin "5") (pinfunction "VOUT_5") (pintype "power_in"))
    )
    (net (code "4") (name "+1.8") (class "Default")
      (node (ref "C29") (pin "1") (pinfunction "1_1") (pintype "passive"))
      (node (ref "C3") (pin "2") (pinfunction "2_2") (pintype "passive"))
      (node (ref "C34") (pin "1") (pinfunction "1_1") (pintype "passive"))
      (node (ref "C35") (pin "2") (pinfunction "2_2") (pintype "passive"))
      (node (ref "C4") (pin "1") (pinfunction "1_1") (pintype "passive"))
      (node (ref "C41") (pin "1") (pinfunction "1_1") (pintype "passive"))
      (node (ref "C70") (pin "1") (pinfunction "1_1") (pintype "passive"))
      (node (ref "C71") (pin "1") (pinfunction "1_1") (pintype "passive"))
      (node (ref "C72") (pin "1") (pinfunction "1_1") (pintype "passive"))
      (node (ref "C73") (pin "1") (pinfunction "1_1") (pintype "passive"))
      (node (ref "C74") (pin "1") (pinfunction "1_1") (pintype "passive"))
      (node (ref "C75") (pin "1") (pinfunction "1_1") (pintype "passive"))
      (node (ref "C76") (pin "1") (pinfunction "1_1") (pintype "passive"))
      (node (ref "C77") (pin "1") (pinfunction "1_1") (pintype "passive"))
      (node (ref "C83") (pin "1") (pinfunction "1_1") (pintype "passive"))
      (node (ref "C84") (pin "1") (pinfunction "1_1") (pintype "passive"))
      (node (ref "C85") (pin "1") (pinfunction "1_1") (pintype "passive"))
      (node (ref "C86") (pin "1") (pinfunction "1_1") (pintype "passive"))
      (node (ref "C87") (pin "1") (pinfunction "1_1") (pintype "passive"))
      (node (ref "R16") (pin "1") (pinfunction "1_1") (pintype "passive"))
      (node (ref "U8") (pin "4") (pinfunction "VOUT_4") (pintype "power_in"))
      (node (ref "U8") (pin "5") (pinfunction "VOUT_5") (pintype "power_in"))
    )
    (net (code "5") (name "+3.3") (class "Default")
      (node (ref "C104") (pin "2") (pinfunction "2_2") (pintype "passive"))
      (node (ref "C105") (pin "1") (pinfunction "1_1") (pintype "passive"))
      (node (ref "C106") (pin "1") (pinfunction "1_1") (pintype "passive"))
      (node (ref "C13") (pin "2") (pinfunction "2_2") (pintype "passive"))
      (node (ref "C32") (pin "1") (pinfunction "1_1") (pintype "passive"))
      (node (ref "C55") (pin "1") (pinfunction "1_1") (pintype "passive"))
      (node (ref "C56") (pin "1") (pinfunction "1_1") (pintype "passive"))
      (node (ref "C57") (pin "1") (pinfunction "1_1") (pintype "passive"))
      (node (ref "C58") (pin "1") (pinfunction "1_1") (pintype "passive"))
      (node (ref "C59") (pin "1") (pinfunction "1_1") (pintype "passive"))
      (node (ref "C60") (pin "1") (pinfunction "1_1") (pintype "passive"))
      (node (ref "C61") (pin "1") (pinfunction "1_1") (pintype "passive"))
      (node (ref "C62") (pin "1") (pinfunction "1_1") (pintype "passive"))
      (node (ref "C63") (pin "1") (pinfunction "1_1") (pintype "passive"))
      (node (ref "D5") (pin "2") (pinfunction "A_2") (pintype "passive"))
      (node (ref "R29") (pin "1") (pinfunction "1_1") (pintype "passive"))
      (node (ref "U11") (pin "4") (pinfunction "VOUT_4") (pintype "power_in"))
      (node (ref "U11") (pin "5") (pinfunction "VOUT_5") (pintype "power_in"))
    )
    (net (code "6") (name "/VCC13_PG") (class "Default")
      (node (ref "R14") (pin "2") (pinfunction "2_2") (pintype "passive"))
      (node (ref "U7") (pin "7") (pinfunction "PG_7") (pintype "open_collector"))
      (node (ref "U8") (pin "1") (pinfunction "EN_1") (pintype "input"))
    )
    (net (code "7") (name "/VCC15_PG") (class "Default")
      (node (ref "R20") (pin "2") (pinfunction "2_2") (pintype "passive"))
      (node (ref "U11") (pin "1") (pinfunction "EN_1") (pintype "input"))
      (node (ref "U9") (pin "7") (pinfunction "PG_7") (pintype "open_collector"))
    )
    (net (code "8") (name "/VCC18_PG") (class "Default")
      (node (ref "R17") (pin "2") (pinfunction "2_2") (pintype "passive"))
      (node (ref "U8") (pin "7") (pinfunction "PG_7") (pintype "open_collector"))
      (node (ref "U9") (pin "1") (pinfunction "EN_1") (pintype "input"))
    )
    (net (code "9") (name "/VCC33_PG") (class "Default")
      (node (ref "R30") (pin "2") (pinfunction "2_2") (pintype "passive"))
      (node (ref "U11") (pin "7") (pinfunction "PG_7") (pintype "open_collector"))
    )
    (net (code "10") (name "/VCCINT_PG") (class "Default")
      (node (ref "R11") (pin "2") (pinfunction "2_2") (pintype "passive"))
      (node (ref "U6") (pin "7") (pinfunction "PG_7") (pintype "open_collector"))
      (node (ref "U7") (pin "1") (pinfunction "EN_1") (pintype "input"))
    )
    (net (code "11") (name "1P3V_A") (class "Default")
      (node (ref "C89") (pin "1") (pinfunction "1_1") (pintype "passive"))
      (node (ref "C90") (pin "1") (pinfunction "1_1") (pintype "passive"))
      (node (ref "C91") (pin "1") (pinfunction "1_1") (pintype "passive"))
      (node (ref "C92") (pin "1") (pinfunction "1_1") (pintype "passive"))
    )
    (net (code "12") (name "GND") (class "Default")
      (node (ref "C100") (pin "1") (pinfunction "1_1") (pintype "passive"))
      (node (ref "C101") (pin "1") (pinfunction "1_1") (pintype "passive"))
      (node (ref "C102") (pin "1") (pinfunction "1_1") (pintype "passive"))
      (node (ref "C103") (pin "1") (pinfunction "1_1") (pintype "passive"))
      (node (ref "C104") (pin "1") (pinfunction "1_1") (pintype "passive"))
      (node (ref "C105") (pin "2") (pinfunction "2_2") (pintype "passive"))
      (node (ref "C106") (pin "2") (pinfunction "2_2") (pintype "passive"))
      (node (ref "C12") (pin "2") (pinfunction "2_2") (pintype "passive"))
      (node (ref "C13") (pin "1") (pinfunction "1_1") (pintype "passive"))
      (node (ref "C130") (pin "2") (pinfunction "2_2") (pintype "passive"))
      (node (ref "C131") (pin "2") (pinfunction "2_2") (pintype "passive"))
      (node (ref "C132") (pin "2") (pinfunction "2_2") (pintype "passive"))
      (node (ref "C133") (pin "2") (pinfunction "2_2") (pintype "passive"))
      (node (ref "C134") (pin "2") (pinfunction "2_2") (pintype "passive"))
      (node (ref "C135") (pin "2") (pinfunction "2_2") (pintype "passive"))
      (node (ref "C136") (pin "2") (pinfunction "2_2") (pintype "passive"))
      (node (ref "C137") (pin "2") (pinfunction "2_2") (pintype "passive"))
      (node (ref "C138") (pin "2") (pinfunction "2_2") (pintype "passive"))
      (node (ref "C139") (pin "2") (pinfunction "2_2") (pintype "passive"))
      (node (ref "C141") (pin "1") (pinfunction "1_1") (pintype "passive"))
      (node (ref "C142") (pin "1") (pinfunction "1_1") (pintype "passive"))
      (node (ref "C144") (pin "1") (pinfunction "C_1") (pintype "passive"))
      (node (ref "C145") (pin "1") (pinfunction "C_1") (pintype "passive"))
      (node (ref "C15") (pin "1") (pinfunction "1_1") (pintype "passive"))
      (node (ref "C2") (pin "2") (pinfunction "2_2") (pintype "passive"))
      (node (ref "C21") (pin "2") (pinfunction "2_2") (pintype "passive"))
      (node (ref "C22") (pin "2") (pinfunction "2_2") (pintype "passive"))
      (node (ref "C25") (pin "2") (pinfunction "2_2") (pintype "passive"))
      (node (ref "C26") (pin "2") (pinfunction "2_2") (pintype "passive"))
      (node (ref "C27") (pin "1") (pinfunction "1_1") (pintype "passive"))
      (node (ref "C28") (pin "1") (pinfunction "1_1") (pintype "passive"))
      (node (ref "C29") (pin "2") (pinfunction "2_2") (pintype "passive"))
      (node (ref "C3") (pin "1") (pinfunction "1_1") (pintype "passive"))
      (node (ref "C30") (pin "1") (pinfunction "1_1") (pintype "passive"))
      (node (ref "C31") (pin "1") (pinfunction "1_1") (pintype "passive"))
      (node (ref "C32") (pin "2") (pinfunction "2_2") (pintype "passive"))
      (node (ref "C34") (pin "2") (pinfunction "2_2") (pintype "passive"))
      (node (ref "C35") (pin "1") (pinfunction "1_1") (pintype "passive"))
      (node (ref "C36") (pin "2") (pinfunction "2_2") (pintype "passive"))
      (node (ref "C37") (pin "2") (pinfunction "2_2") (pintype "passive"))
      (node (ref "C38") (pin "2") (pinfunction "2_2") (pintype "passive"))
      (node (ref "C39") (pin "2") (pinfunction "2_2") (pintype "passive"))
      (node (ref "C4") (pin "2") (pinfunction "2_2") (pintype "passive"))
      (node (ref "C40") (pin "2") (pinfunction "2_2") (pintype "passive"))
      (node (ref "C41") (pin "2") (pinfunction "2_2") (pintype "passive"))
      (node (ref "C42") (pin "2") (pinfunction "2_2") (pintype "passive"))
      (node (ref "C44") (pin "2") (pinfunction "2_2") (pintype "passive"))
      (node (ref "C45") (pin "2") (pinfunction "2_2") (pintype "passive"))
      (node (ref "C46") (pin "2") (pinfunction "2_2") (pintype "passive"))
      (node (ref "C47") (pin "2") (pinfunction "2_2") (pintype "passive"))
      (node (ref "C48") (pin "2") (pinfunction "2_2") (pintype "passive"))
      (node (ref "C49") (pin "2") (pinfunction "2_2") (pintype "passive"))
      (node (ref "C5") (pin "1") (pinfunction "1_1") (pintype "passive"))
      (node (ref "C50") (pin "2") (pinfunction "2_2") (pintype "passive"))
      (node (ref "C51") (pin "2") (pinfunction "2_2") (pintype "passive"))
      (node (ref "C52") (pin "2") (pinfunction "2_2") (pintype "passive"))
      (node (ref "C53") (pin "2") (pinfunction "2_2") (pintype "passive"))
      (node (ref "C54") (pin "1") (pinfunction "1_1") (pintype "passive"))
      (node (ref "C55") (pin "2") (pinfunction "2_2") (pintype "passive"))
      (node (ref "C56") (pin "2") (pinfunction "2_2") (pintype "passive"))
      (node (ref "C57") (pin "2") (pinfunction "2_2") (pintype "passive"))
      (node (ref "C58") (pin "2") (pinfunction "2_2") (pintype "passive"))
      (node (ref "C59") (pin "2") (pinfunction "2_2") (pintype "passive"))
      (node (ref "C6") (pin "2") (pinfunction "2_2") (pintype "passive"))
      (node (ref "C60") (pin "2") (pinfunction "2_2") (pintype "passive"))
      (node (ref "C61") (pin "2") (pinfunction "2_2") (pintype "passive"))
      (node (ref "C62") (pin "2") (pinfunction "2_2") (pintype "passive"))
      (node (ref "C63") (pin "2") (pinfunction "2_2") (pintype "passive"))
      (node (ref "C64") (pin "2") (pinfunction "2_2") (pintype "passive"))
      (node (ref "C65") (pin "2") (pinfunction "2_2") (pintype "passive"))
      (node (ref "C66") (pin "2") (pinfunction "2_2") (pintype "passive"))
      (node (ref "C67") (pin "2") (pinfunction "2_2") (pintype "passive"))
      (node (ref "C68") (pin "2") (pinfunction "2_2") (pintype "passive"))
      (node (ref "C69") (pin "2") (pinfunction "2_2") (pintype "passive"))
      (node (ref "C70") (pin "2") (pinfunction "2_2") (pintype "passive"))
      (node (ref "C71") (pin "2") (pinfunction "2_2") (pintype "passive"))
      (node (ref "C72") (pin "2") (pinfunction "2_2") (pintype "passive"))
      (node (ref "C73") (pin "2") (pinfunction "2_2") (pintype "passive"))
      (node (ref "C74") (pin "2") (pinfunction "2_2") (pintype "passive"))
      (node (ref "C75") (pin "2") (pinfunction "2_2") (pintype "passive"))
      (node (ref "C76") (pin "2") (pinfunction "2_2") (pintype "passive"))
      (node (ref "C77") (pin "2") (pinfunction "2_2") (pintype "passive"))
      (node (ref "C78") (pin "2") (pinfunction "2_2") (pintype "passive"))
      (node (ref "C79") (pin "2") (pinfunction "2_2") (pintype "passive"))
      (node (ref "C80") (pin "2") (pinfunction "2_2") (pintype "passive"))
      (node (ref "C81") (pin "2") (pinfunction "2_2") (pintype "passive"))
      (node (ref "C82") (pin "2") (pinfunction "2_2") (pintype "passive"))
      (node (ref "C83") (pin "2") (pinfunction "2_2") (pintype "passive"))
      (node (ref "C84") (pin "2") (pinfunction "2_2") (pintype "passive"))
      (node (ref "C85") (pin "2") (pinfunction "2_2") (pintype "passive"))
      (node (ref "C86") (pin "2") (pinfunction "2_2") (pintype "passive"))
      (node (ref "C87") (pin "2") (pinfunction "2_2") (pintype "passive"))
      (node (ref "C88") (pin "1") (pinfunction "1_1") (pintype "passive"))
      (node (ref "C89") (pin "2") (pinfunction "2_2") (pintype "passive"))
      (node (ref "C90") (pin "2") (pinfunction "2_2") (pintype "passive"))
      (node (ref "C91") (pin "2") (pinfunction "2_2") (pintype "passive"))
      (node (ref "C92") (pin "2") (pinfunction "2_2") (pintype "passive"))
      (node (ref "C93") (pin "2") (pinfunction "2_2") (pintype "passive"))
      (node (ref "C94") (pin "2") (pinfunction "2_2") (pintype "passive"))
      (node (ref "C95") (pin "2") (pinfunction "2_2") (pintype "passive"))
      (node (ref "C96") (pin "2") (pinfunction "2_2") (pintype "passive"))
      (node (ref "C97") (pin "2") (pinfunction "2_2") (pintype "passive"))
      (node (ref "C98") (pin "2") (pinfunction "2_2") (pintype "passive"))
      (node (ref "C99") (pin "2") (pinfunction "2_2") (pintype "passive"))
      (node (ref "R12") (pin "2") (pinfunction "2_2") (pintype "passive"))
      (node (ref "R15") (pin "2") (pinfunction "2_2") (pintype "passive"))
      (node (ref "R18") (pin "2") (pinfunction "2_2") (pintype "passive"))
      (node (ref "R28") (pin "2") (pinfunction "2_2") (pintype "passive"))
      (node (ref "R71") (pin "1") (pinfunction "1_1") (pintype "passive"))
      (node (ref "R9") (pin "2") (pinfunction "2_2") (pintype "passive"))
      (node (ref "U11") (pin "3") (pinfunction "GND_3") (pintype "power_in"))
      (node (ref "U11") (pin "9") (pinfunction "EP_9") (pintype "power_in"))
      (node (ref "U6") (pin "3") (pinfunction "GND_3") (pintype "power_in"))
      (node (ref "U6") (pin "9") (pinfunction "EP_9") (pintype "power_in"))
      (node (ref "U7") (pin "3") (pinfunction "GND_3") (pintype "power_in"))
      (node (ref "U7") (pin "9") (pinfunction "EP_9") (pintype "power_in"))
      (node (ref "U8") (pin "3") (pinfunction "GND_3") (pintype "power_in"))
      (node (ref "U8") (pin "9") (pinfunction "EP_9") (pintype "power_in"))
      (node (ref "U9") (pin "3") (pinfunction "GND_3") (pintype "power_in"))
      (node (ref "U9") (pin "9") (pinfunction "EP_9") (pintype "power_in"))
      (node (ref "pwr-") (pin "1") (pinfunction "Pin_1") (pintype "passive"))
      (node (ref "pwr-1") (pin "1") (pinfunction "Pin_1") (pintype "passive"))
    )
    (net (code "13") (name "Net-(C15-Pad2)") (class "Default")
      (node (ref "C15") (pin "2") (pinfunction "2_2") (pintype "passive"))
      (node (ref "L2") (pin "1") (pinfunction "1_1") (pintype "passive"))
      (node (ref "R13") (pin "1") (pinfunction "1_1") (pintype "passive"))
      (node (ref "U7") (pin "4") (pinfunction "VOUT_4") (pintype "power_in"))
      (node (ref "U7") (pin "5") (pinfunction "VOUT_5") (pintype "power_in"))
    )
    (net (code "14") (name "Net-(D5-C)") (class "Default")
      (node (ref "D5") (pin "1") (pinfunction "C_1") (pintype "passive"))
      (node (ref "R71") (pin "2") (pinfunction "2_2") (pintype "passive"))
    )
    (net (code "15") (name "Net-(U6-FB)") (class "Default")
      (node (ref "R10") (pin "2") (pinfunction "2_2") (pintype "passive"))
      (node (ref "R9") (pin "1") (pinfunction "1_1") (pintype "passive"))
      (node (ref "U6") (pin "6") (pinfunction "FB_6") (pintype "input"))
    )
    (net (code "16") (name "Net-(U6-SS{slash}TR)") (class "Default")
      (node (ref "C54") (pin "2") (pinfunction "2_2") (pintype "passive"))
      (node (ref "U6") (pin "8") (pinfunction "SS/TR_8") (pintype "input"))
    )
    (net (code "17") (name "Net-(U7-FB)") (class "Default")
      (node (ref "R12") (pin "1") (pinfunction "1_1") (pintype "passive"))
      (node (ref "R13") (pin "2") (pinfunction "2_2") (pintype "passive"))
      (node (ref "U7") (pin "6") (pinfunction "FB_6") (pintype "input"))
    )
    (net (code "18") (name "Net-(U7-SS{slash}TR)") (class "Default")
      (node (ref "C31") (pin "2") (pinfunction "2_2") (pintype "passive"))
      (node (ref "U7") (pin "8") (pinfunction "SS/TR_8") (pintype "input"))
    )
    (net (code "19") (name "Net-(U8-FB)") (class "Default")
      (node (ref "R15") (pin "1") (pinfunction "1_1") (pintype "passive"))
      (node (ref "R16") (pin "2") (pinfunction "2_2") (pintype "passive"))
      (node (ref "U8") (pin "6") (pinfunction "FB_6") (pintype "input"))
    )
    (net (code "20") (name "Net-(U8-SS{slash}TR)") (class "Default")
      (node (ref "C100") (pin "2") (pinfunction "2_2") (pintype "passive"))
      (node (ref "U8") (pin "8") (pinfunction "SS/TR_8") (pintype "input"))
    )
    (net (code "21") (name "Net-(U9-FB)") (class "Default")
      (node (ref "R18") (pin "1") (pinfunction "1_1") (pintype "passive"))
      (node (ref "R19") (pin "2") (pinfunction "2_2") (pintype "passive"))
      (node (ref "U9") (pin "6") (pinfunction "FB_6") (pintype "input"))
    )
    (net (code "22") (name "Net-(U9-SS{slash}TR)") (class "Default")
      (node (ref "C103") (pin "2") (pinfunction "2_2") (pintype "passive"))
      (node (ref "U9") (pin "8") (pinfunction "SS/TR_8") (pintype "input"))
    )
    (net (code "23") (name "Net-(U11-FB)") (class "Default")
      (node (ref "R28") (pin "1") (pinfunction "1_1") (pintype "passive"))
      (node (ref "R29") (pin "2") (pinfunction "2_2") (pintype "passive"))
      (node (ref "U11") (pin "6") (pinfunction "FB_6") (pintype "input"))
    )
    (net (code "24") (name "Net-(U11-SS{slash}TR)") (class "Default")
      (node (ref "C142") (pin "2") (pinfunction "2_2") (pintype "passive"))
      (node (ref "U11") (pin "8") (pinfunction "SS/TR_8") (pintype "input"))
    )
    (net (code "25") (name "VIN") (class "Default")
      (node (ref "C102") (pin "2") (pinfunction "2_2") (pintype "passive"))
      (node (ref "C139") (pin "1") (pinfunction "1_1") (pintype "passive"))
      (node (ref "C141") (pin "2") (pinfunction "2_2") (pintype "passive"))
      (node (ref "C144") (pin "2") (pinfunction "A_2") (pintype "passive"))
      (node (ref "C145") (pin "2") (pinfunction "A_2") (pintype "passive"))
      (node (ref "C21") (pin "1") (pinfunction "1_1") (pintype "passive"))
      (node (ref "C22") (pin "1") (pinfunction "1_1") (pintype "passive"))
      (node (ref "C28") (pin "2") (pinfunction "2_2") (pintype "passive"))
      (node (ref "C30") (pin "2") (pinfunction "2_2") (pintype "passive"))
      (node (ref "C88") (pin "2") (pinfunction "2_2") (pintype "passive"))
      (node (ref "R11") (pin "1") (pinfunction "1_1") (pintype "passive"))
      (node (ref "R14") (pin "1") (pinfunction "1_1") (pintype "passive"))
      (node (ref "R17") (pin "1") (pinfunction "1_1") (pintype "passive"))
      (node (ref "R20") (pin "1") (pinfunction "1_1") (pintype "passive"))
      (node (ref "R30") (pin "1") (pinfunction "1_1") (pintype "passive"))
      (node (ref "U11") (pin "2") (pinfunction "VIN_2") (pintype "power_in"))
      (node (ref "U6") (pin "1") (pinfunction "EN_1") (pintype "input"))
      (node (ref "U6") (pin "2") (pinfunction "VIN_2") (pintype "power_in"))
      (node (ref "U7") (pin "2") (pinfunction "VIN_2") (pintype "power_in"))
      (node (ref "U8") (pin "2") (pinfunction "VIN_2") (pintype "power_in"))
      (node (ref "U9") (pin "2") (pinfunction "VIN_2") (pintype "power_in"))
      (node (ref "pwr+") (pin "1") (pinfunction "Pin_1") (pintype "passive"))
      (node (ref "pwr+1") (pin "1") (pinfunction "Pin_1") (pintype "passive"))
    )
    (net (code "26") (name "VTTREF") (class "Default")
      (node (ref "C130") (pin "1") (pinfunction "1_1") (pintype "passive"))
      (node (ref "C131") (pin "1") (pinfunction "1_1") (pintype "passive"))
      (node (ref "C132") (pin "1") (pinfunction "1_1") (pintype "passive"))
      (node (ref "C133") (pin "1") (pinfunction "1_1") (pintype "passive"))
      (node (ref "C134") (pin "1") (pinfunction "1_1") (pintype "passive"))
      (node (ref "C135") (pin "1") (pinfunction "1_1") (pintype "passive"))
      (node (ref "C136") (pin "1") (pinfunction "1_1") (pintype "passive"))
      (node (ref "C137") (pin "1") (pinfunction "1_1") (pintype "passive"))
      (node (ref "C138") (pin "1") (pinfunction "1_1") (pintype "passive"))
    )
  )
)
